# Power.net
KiCad netlist of a schematic drawn in Altium Designer
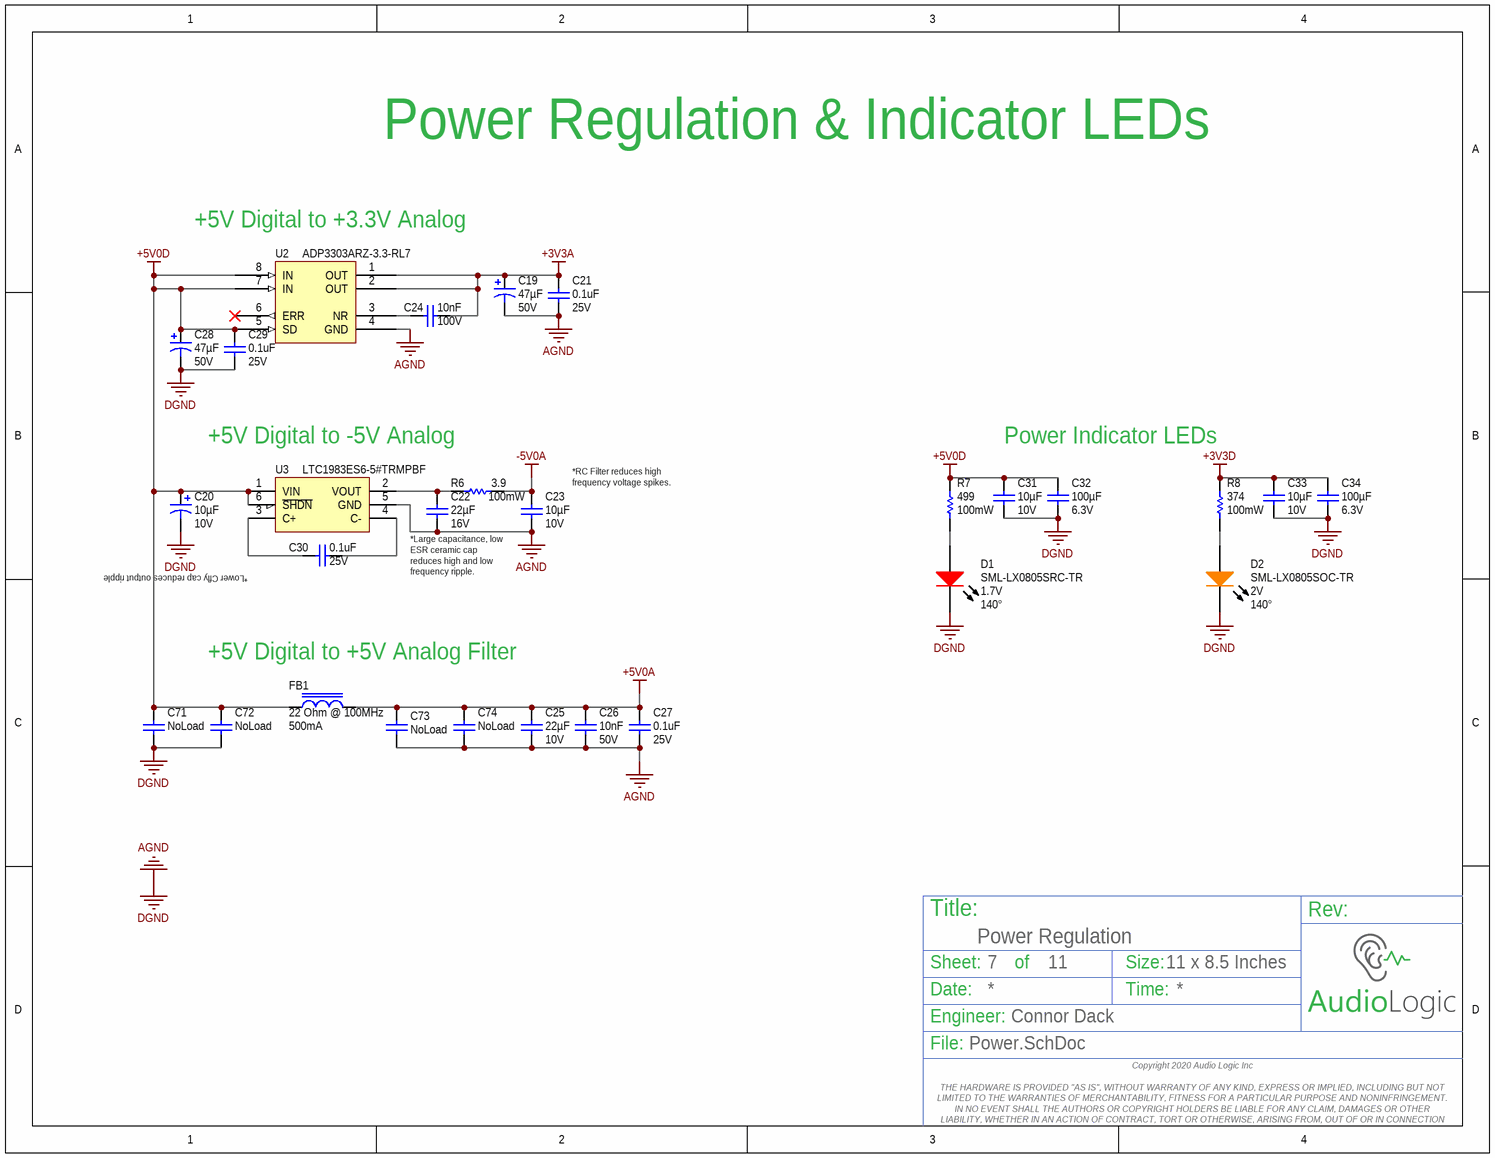
[diagram p0: Power.SchDoc]

(export (version "E")
  (design (tool "Eeschema 10.0.6"))
  (components
    (comp (ref "C19")
      (value "EEE-FT1H470AP")
      (footprint "ALUMCAPC630D_D")
      (description "CAP ALUM 47UF 50V 20% SMD")
      (fields
        (field (name "MANUFACTURER") "Panasonic - ECG")
        (field (name "VOLTAGE RATING") "50V")
        (field (name "TOLERANCE") "±20%")
        (field (name "CAPACITANCE") "47µF")
      )
      (libsource (lib "Schematic_Components") (part "EEE-FT1H470AP"))
    )
    (comp (ref "C20")
      (value "TPSA106K010R0900")
      (footprint "C1206_TANT")
      (description "CAP TANT 10UF 10V 10% 1206")
      (fields
        (field (name "MANUFACTURER") "AVX Corporation")
        (field (name "VOLTAGE - RATED") "10V")
        (field (name "TOLERANCE") "±10%")
        (field (name "CAPACITANCE") "10µF")
      )
      (libsource (lib "Schematic_Components") (part "TPSA106K010R0900"))
    )
    (comp (ref "C21")
      (value "CGA3E2X7R1E104K080AA")
      (footprint "3-0603_L")
      (description "CAP CER 0.1UF 25V X7R 0603")
      (fields
        (field (name "MANUFACTURER") "TDK")
        (field (name "TOLERANCE") "10%")
        (field (name "VOLTAGE RATING") "25V")
        (field (name "CAPACITANCE") "0.1uF")
      )
      (libsource (lib "Schematic_Components_CD") (part "CGA3E2X7R1E104K080AA"))
    )
    (comp (ref "C22")
      (value "C3216X6S1C226M")
      (footprint "C1206")
      (description "CAP CER 22UF 16V 20% X6S 1206")
      (fields
        (field (name "MANUFACTURER") "TDK Corporation")
        (field (name "VOLTAGE - RATED") "16V")
        (field (name "TOLERANCE") "±20%")
        (field (name "CAPACITANCE") "22µF")
      )
      (libsource (lib "Schematic_Components") (part "C3216X6S1C226M"))
    )
    (comp (ref "C23")
      (value "C1608X5R1A106K")
      (footprint "3-0603_L")
      (description "CAP CER 10UF 10V 10% X5R 0603")
      (fields
        (field (name "MANUFACTURER") "TDK Corporation")
        (field (name "VOLTAGE - RATED") "10V")
        (field (name "TOLERANCE") "±10%")
        (field (name "CAPACITANCE") "10µF")
      )
      (libsource (lib "Schematic_Components") (part "C1608X5R1A106K"))
    )
    (comp (ref "C24")
      (value "C1608X7R2A103K080AA")
      (footprint "3-0603_L")
      (description "CAP CER 10000PF 100V X7R 0603")
      (fields
        (field (name "MANUFACTURER") "TDK Corporation")
        (field (name "VOLTAGE - RATED") "100V")
        (field (name "TOLERANCE") "±10%")
        (field (name "CAPACITANCE") "10nF")
      )
      (libsource (lib "Schematic_Components") (part "C1608X7R2A103K080AA"))
    )
    (comp (ref "C25")
      (value "CL21A226KPCLRNC")
      (footprint "6-0805_L")
      (description "CAP CER 22UF 10V X5R 0805")
      (fields
        (field (name "MANUFACTURER") "Samsung Electro-Mechanics America, Inc.")
        (field (name "TOLERANCE") "±10%")
        (field (name "VOLTAGE - RATED") "10V")
        (field (name "CAPACITANCE") "22µF")
      )
      (libsource (lib "Schematic_Components") (part "CL21A226KPCLRNC"))
    )
    (comp (ref "C26")
      (value "C0603C103J5RACTU")
      (footprint "3-0603_L")
      (description "CAP CER 10000PF 50V 5% X7R 0603")
      (fields
        (field (name "MANUFACTURER") "Kemet")
        (field (name "VOLTAGE - RATED") "50V")
        (field (name "TOLERANCE") "±5%")
        (field (name "CAPACITANCE") "10nF")
      )
      (libsource (lib "Schematic_Components") (part "C0603C103J5RACTU"))
    )
    (comp (ref "C27")
      (value "CGA3E2X7R1E104K080AA")
      (footprint "3-0603_L")
      (description "CAP CER 0.1UF 25V X7R 0603")
      (fields
        (field (name "MANUFACTURER") "TDK")
        (field (name "TOLERANCE") "10%")
        (field (name "VOLTAGE RATING") "25V")
        (field (name "CAPACITANCE") "0.1uF")
      )
      (libsource (lib "Schematic_Components_CD") (part "CGA3E2X7R1E104K080AA"))
    )
    (comp (ref "C28")
      (value "EEE-FT1H470AP")
      (footprint "ALUMCAPC630D_D")
      (description "CAP ALUM 47UF 50V 20% SMD")
      (fields
        (field (name "MANUFACTURER") "Panasonic - ECG")
        (field (name "VOLTAGE RATING") "50V")
        (field (name "TOLERANCE") "±20%")
        (field (name "CAPACITANCE") "47µF")
      )
      (libsource (lib "Schematic_Components") (part "EEE-FT1H470AP"))
    )
    (comp (ref "C29")
      (value "CGA3E2X7R1E104K080AA")
      (footprint "3-0603_L")
      (description "CAP CER 0.1UF 25V X7R 0603")
      (fields
        (field (name "MANUFACTURER") "TDK")
        (field (name "TOLERANCE") "10%")
        (field (name "VOLTAGE RATING") "25V")
        (field (name "CAPACITANCE") "0.1uF")
      )
      (libsource (lib "Schematic_Components_CD") (part "CGA3E2X7R1E104K080AA"))
    )
    (comp (ref "C30")
      (value "CGA3E2X7R1E104K080AA")
      (footprint "3-0603_L")
      (description "CAP CER 0.1UF 25V X7R 0603")
      (fields
        (field (name "MANUFACTURER") "TDK")
        (field (name "TOLERANCE") "10%")
        (field (name "VOLTAGE RATING") "25V")
        (field (name "CAPACITANCE") "0.1uF")
      )
      (libsource (lib "Schematic_Components_CD") (part "CGA3E2X7R1E104K080AA"))
    )
    (comp (ref "C31")
      (value "C1608X5R1A106K")
      (footprint "3-0603_L")
      (description "CAP CER 10UF 10V 10% X5R 0603")
      (fields
        (field (name "MANUFACTURER") "TDK Corporation")
        (field (name "VOLTAGE - RATED") "10V")
        (field (name "TOLERANCE") "±10%")
        (field (name "CAPACITANCE") "10µF")
      )
      (libsource (lib "Schematic_Components") (part "C1608X5R1A106K"))
    )
    (comp (ref "C32")
      (value "CL32X107MQVNNNE")
      (footprint "C1210X25_L")
      (description "100µF 6.3V Ceramic Capacitor X6S 1210 (3225 Metric) 0.126\" L x 0.098\" W (3.20mm x 2.50mm)")
      (fields
        (field (name "MANUFACTURER") "Samsung Electro-Mechanics America, Inc.")
        (field (name "TOLERANCE") "±20%")
        (field (name "VOLTAGE - RATED") "6.3V")
        (field (name "CAPACITANCE") "100µF")
      )
      (libsource (lib "Schematic_Components") (part "CL32X107MQVNNNE"))
    )
    (comp (ref "C33")
      (value "C1608X5R1A106K")
      (footprint "3-0603_L")
      (description "CAP CER 10UF 10V 10% X5R 0603")
      (fields
        (field (name "MANUFACTURER") "TDK Corporation")
        (field (name "VOLTAGE - RATED") "10V")
        (field (name "TOLERANCE") "±10%")
        (field (name "CAPACITANCE") "10µF")
      )
      (libsource (lib "Schematic_Components") (part "C1608X5R1A106K"))
    )
    (comp (ref "C34")
      (value "CL32X107MQVNNNE")
      (footprint "C1210X25_L")
      (description "100µF 6.3V Ceramic Capacitor X6S 1210 (3225 Metric) 0.126\" L x 0.098\" W (3.20mm x 2.50mm)")
      (fields
        (field (name "MANUFACTURER") "Samsung Electro-Mechanics America, Inc.")
        (field (name "TOLERANCE") "±20%")
        (field (name "VOLTAGE - RATED") "6.3V")
        (field (name "CAPACITANCE") "100µF")
      )
      (libsource (lib "Schematic_Components") (part "CL32X107MQVNNNE"))
    )
    (comp (ref "C71")
      (value "CAP 0603")
      (footprint "3-0603_L_DNP")
      (description "CAP 0603 SMD - NoLoad")
      (fields (field (name "CAPACITANCE") "NoLoad"))
      (libsource (lib "Schematic_Components_CD") (part "CAP 0603"))
    )
    (comp (ref "C72")
      (value "CAP 0603")
      (footprint "3-0603_L_DNP")
      (description "CAP 0603 SMD - NoLoad")
      (fields (field (name "CAPACITANCE") "NoLoad"))
      (libsource (lib "Schematic_Components_CD") (part "CAP 0603"))
    )
    (comp (ref "C73")
      (value "CAP 0603")
      (footprint "3-0603_L_DNP")
      (description "CAP 0603 SMD - NoLoad")
      (fields (field (name "CAPACITANCE") "NoLoad"))
      (libsource (lib "Schematic_Components_CD") (part "CAP 0603"))
    )
    (comp (ref "C74")
      (value "CAP 0603")
      (footprint "3-0603_L_DNP")
      (description "CAP 0603 SMD - NoLoad")
      (fields (field (name "CAPACITANCE") "NoLoad"))
      (libsource (lib "Schematic_Components_CD") (part "CAP 0603"))
    )
    (comp (ref "D1")
      (value "LED_RED 4")
      (footprint "DIOM2012X12L_RED")
      (description "LED 660NM SUPER RED CLR 0805 T/R")
      (fields
        (field (name "MANUFACTURER") "Lumex Opto/Components Inc")
        (field (name "MANUFACTURER PART NUMBER") "SML-LX0805SRC-TR")
        (field (name "VOLTAGE - FORWARD (VF) (TYP)") "1.7V")
        (field (name "VIEWING ANGLE") "140°")
      )
      (libsource (lib "Schematic_Components") (part "LED_RED 4"))
    )
    (comp (ref "D2")
      (value "LED_ORANGE 3")
      (footprint "DIOM2012X12L_ORANGE")
      (description "LED 610NM SUPER ORANGE 0805 SMD")
      (fields
        (field (name "MANUFACTURER") "Lumex Opto/Components Inc")
        (field (name "MANUFACTURER PART NUMBER") "SML-LX0805SOC-TR")
        (field (name "VOLTAGE - FORWARD (VF) (TYP)") "2V")
        (field (name "VIEWING ANGLE") "140°")
      )
      (libsource (lib "Schematic_Components") (part "LED_ORANGE 3"))
    )
    (comp (ref "FB1")
      (value "BLM18BA220SN1D")
      (footprint "3-0603_L")
      (description "FERRITE CHIP 22 OHM 500MA 0603")
      (fields
        (field (name "MANUFACTURER") "Murata Electronics North America")
        (field (name "CURRENT RATING") "500mA")
        (field (name "IMPEDANCE @ FREQUENCY") "22 Ohm @ 100MHz")
      )
      (libsource (lib "Schematic_Components") (part "BLM18BA220SN1D"))
    )
    (comp (ref "R6")
      (value "ERJ-3RQF3R9V")
      (footprint "3-0603_R_L")
      (description "RES 3.9 OHM 1/10W 1% 0603 SMD")
      (fields
        (field (name "MANUFACTURER") "Panasonic Electronic Components")
        (field (name "TOLERANCE") "±1%")
        (field (name "POWER (WATTS)") "100mW")
        (field (name "RESISTANCE (OHMS)") "3.9")
      )
      (libsource (lib "Schematic_Components") (part "ERJ-3RQF3R9V"))
    )
    (comp (ref "R7")
      (value "ERJ-3EKF4990V")
      (footprint "3-0603_R_L")
      (description "RES 499 OHM 1/10W 1% 0603 SMD")
      (fields
        (field (name "MANUFACTURER") "Panasonic - ECG")
        (field (name "POWER (WATTS)") "100mW")
        (field (name "TOLERANCE") "±1%")
        (field (name "RESISTANCE (OHMS)") "499")
      )
      (libsource (lib "Schematic_Components") (part "ERJ-3EKF4990V"))
    )
    (comp (ref "R8")
      (value "ERJ-3EKF3740V")
      (footprint "3-0603_R_L")
      (description "RES SMD 374 OHM 1% 1/10W 0603")
      (fields
        (field (name "MANUFACTURER") "Panasonic Electronic Components")
        (field (name "TOLERANCE") "±1%")
        (field (name "POWER (WATTS)") "100mW")
        (field (name "RESISTANCE (OHMS)") "374")
      )
      (libsource (lib "Schematic_Components") (part "ERJ-3EKF3740V"))
    )
    (comp (ref "U2")
      (value "ADP3303ARZ-3.3-RL7")
      (footprint "SOIC127P600X175-8N")
      (description "Linear Voltage Regulator IC Positive Fixed 1 Output 3.3V 200mA 8-SOIC")
      (fields
        (field (name "MANUFACTURER") "Analog Devices Inc.")
        (field (name "MANUFACTURER PART NUMBER") "ADP3303ARZ-3.3-RL7")
      )
      (libsource (lib "Schematic_Components_CD") (part "ADP3303ARZ-3.3-RL7"))
    )
    (comp (ref "U3")
      (value "~")
      (footprint "SOT23-6_L")
      (description "IC REG SWITCHD CAP INV -5V SOT23")
      (fields
        (field (name "MANUFACTURER") "Linear Technology")
        (field (name "MANUFACTURER PART NUMBER") "LTC1983ES6-5#TRMPBF")
      )
      (libsource (lib "Schematic_Components") (part "LTC1983ES6-5#TRMPBF"))
    )
  )
  (nets
    (net (code "1") (name "+3V3A") (class "Default")
      (node (ref "C19") (pin "1") (pinfunction "P_1") (pintype "passive"))
      (node (ref "C21") (pin "1") (pinfunction "1_1") (pintype "passive"))
      (node (ref "C24") (pin "1") (pinfunction "1_1") (pintype "passive"))
      (node (ref "U2") (pin "1") (pinfunction "OUT_1") (pintype "passive"))
      (node (ref "U2") (pin "2") (pinfunction "OUT_2") (pintype "passive"))
    )
    (net (code "2") (name "+3V3D") (class "Default")
      (node (ref "C33") (pin "2") (pinfunction "2_2") (pintype "passive"))
      (node (ref "C34") (pin "2") (pinfunction "2_2") (pintype "passive"))
      (node (ref "R8") (pin "2") (pinfunction "2_2") (pintype "passive"))
    )
    (net (code "3") (name "+5V0A") (class "Default")
      (node (ref "C25") (pin "2") (pinfunction "2_2") (pintype "passive"))
      (node (ref "C26") (pin "2") (pinfunction "2_2") (pintype "passive"))
      (node (ref "C27") (pin "1") (pinfunction "1_1") (pintype "passive"))
      (node (ref "C73") (pin "2") (pinfunction "2_2") (pintype "passive"))
      (node (ref "C74") (pin "2") (pinfunction "2_2") (pintype "passive"))
      (node (ref "FB1") (pin "2") (pinfunction "2_2") (pintype "passive"))
    )
    (net (code "4") (name "+5V0D") (class "Default")
      (node (ref "C20") (pin "1") (pinfunction "P_1") (pintype "passive"))
      (node (ref "C28") (pin "1") (pinfunction "P_1") (pintype "passive"))
      (node (ref "C29") (pin "1") (pinfunction "1_1") (pintype "passive"))
      (node (ref "C31") (pin "2") (pinfunction "2_2") (pintype "passive"))
      (node (ref "C32") (pin "2") (pinfunction "2_2") (pintype "passive"))
      (node (ref "C71") (pin "2") (pinfunction "2_2") (pintype "passive"))
      (node (ref "C72") (pin "2") (pinfunction "2_2") (pintype "passive"))
      (node (ref "FB1") (pin "1") (pinfunction "1_1") (pintype "passive"))
      (node (ref "R7") (pin "2") (pinfunction "2_2") (pintype "passive"))
      (node (ref "U2") (pin "5") (pinfunction "SD_5") (pintype "input"))
      (node (ref "U2") (pin "7") (pinfunction "IN_7") (pintype "input"))
      (node (ref "U2") (pin "8") (pinfunction "IN_8") (pintype "input"))
      (node (ref "U3") (pin "1") (pinfunction "VIN_1") (pintype "power_in"))
      (node (ref "U3") (pin "6") (pinfunction "SHDN_6") (pintype "passive"))
    )
    (net (code "5") (name "-5V0A") (class "Default")
      (node (ref "C23") (pin "2") (pinfunction "2_2") (pintype "passive"))
      (node (ref "R6") (pin "2") (pinfunction "2_2") (pintype "passive"))
    )
    (net (code "6") (name "AGND") (class "Default")
      (node (ref "C19") (pin "2") (pinfunction "N_2") (pintype "passive"))
      (node (ref "C20") (pin "2") (pinfunction "N_2") (pintype "passive"))
      (node (ref "C21") (pin "2") (pinfunction "2_2") (pintype "passive"))
      (node (ref "C22") (pin "1") (pinfunction "1_1") (pintype "passive"))
      (node (ref "C23") (pin "1") (pinfunction "1_1") (pintype "passive"))
      (node (ref "C25") (pin "1") (pinfunction "1_1") (pintype "passive"))
      (node (ref "C26") (pin "1") (pinfunction "1_1") (pintype "passive"))
      (node (ref "C27") (pin "2") (pinfunction "2_2") (pintype "passive"))
      (node (ref "C28") (pin "2") (pinfunction "N_2") (pintype "passive"))
      (node (ref "C29") (pin "2") (pinfunction "2_2") (pintype "passive"))
      (node (ref "C31") (pin "1") (pinfunction "1_1") (pintype "passive"))
      (node (ref "C32") (pin "1") (pinfunction "1_1") (pintype "passive"))
      (node (ref "C33") (pin "1") (pinfunction "1_1") (pintype "passive"))
      (node (ref "C34") (pin "1") (pinfunction "1_1") (pintype "passive"))
      (node (ref "C71") (pin "1") (pinfunction "1_1") (pintype "passive"))
      (node (ref "C72") (pin "1") (pinfunction "1_1") (pintype "passive"))
      (node (ref "C73") (pin "1") (pinfunction "1_1") (pintype "passive"))
      (node (ref "C74") (pin "1") (pinfunction "1_1") (pintype "passive"))
      (node (ref "D1") (pin "2") (pinfunction "K_2") (pintype "passive"))
      (node (ref "D2") (pin "2") (pinfunction "K_2") (pintype "passive"))
      (node (ref "U2") (pin "4") (pinfunction "GND_4") (pintype "passive"))
      (node (ref "U3") (pin "5") (pinfunction "GND_5") (pintype "passive"))
    )
    (net (code "7") (name "Net-(D1-A)") (class "Default")
      (node (ref "D1") (pin "1") (pinfunction "A_1") (pintype "passive"))
      (node (ref "R7") (pin "1") (pinfunction "1_1") (pintype "passive"))
    )
    (net (code "8") (name "Net-(D2-A)") (class "Default")
      (node (ref "D2") (pin "1") (pinfunction "A_1") (pintype "passive"))
      (node (ref "R8") (pin "1") (pinfunction "1_1") (pintype "passive"))
    )
    (net (code "9") (name "Net-(U2-NR)") (class "Default")
      (node (ref "C24") (pin "2") (pinfunction "2_2") (pintype "passive"))
      (node (ref "U2") (pin "3") (pinfunction "NR_3") (pintype "passive"))
    )
    (net (code "10") (name "Net-(U3-C+)") (class "Default")
      (node (ref "C30") (pin "2") (pinfunction "2_2") (pintype "passive"))
      (node (ref "U3") (pin "3") (pinfunction "C+_3") (pintype "passive"))
    )
    (net (code "11") (name "Net-(U3-C-)") (class "Default")
      (node (ref "C30") (pin "1") (pinfunction "1_1") (pintype "passive"))
      (node (ref "U3") (pin "4") (pinfunction "C-_4") (pintype "passive"))
    )
    (net (code "12") (name "Net-(U3-VOUT)") (class "Default")
      (node (ref "C22") (pin "2") (pinfunction "2_2") (pintype "passive"))
      (node (ref "R6") (pin "1") (pinfunction "1_1") (pintype "passive"))
      (node (ref "U3") (pin "2") (pinfunction "VOUT_2") (pintype "power_in"))
    )
    (net (code "13") (name "unconnected-(U2-ERR-Pad6)") (class "Default")
      (node (ref "U2") (pin "6") (pinfunction "ERR_6") (pintype "output+no_connect"))
    )
  )
)
